# Power.net
KiCad netlist of a schematic drawn in Altium Designer
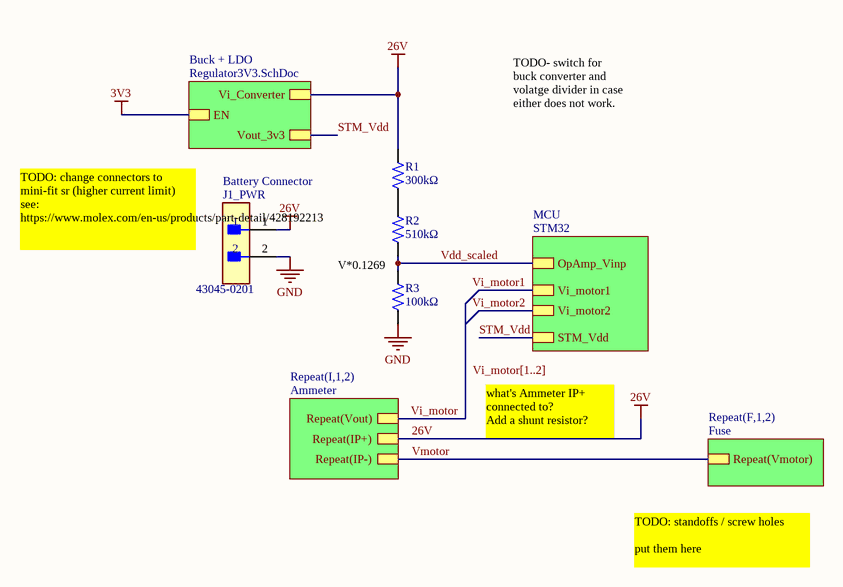
[diagram p0: Power.SchDoc]

(export (version "E")
  (design (tool "Eeschema 10.0.6"))
  (components
    (comp (ref "J1_PWR")
      (value "43045-0201")
      (footprint "FP-43045-0201-MFG")
      (description "CONN HEADER R/A 2POS")
      (libsource (lib "Altium Content Vault") (part "3bc925449376181038e59eaffc5286c"))
    )
    (comp (ref "R1")
      (value "0603WAF3003T5E")
      (footprint "RES-0603")
      (description "Resistor, 300kΩ, ±1%, 100mW, 75V, ±100ppm/℃, -55℃~+155℃, SMD 0603")
      (fields
        (field (name "MANUFACTURER") "Uniroyal")
        (field (name "JLCPCB PART NUMBER") "C23024")
        (field (name "RESISTANCE") "300kΩ")
      )
      (libsource (lib "jlcpcb_2024_10_resistors_basic") (part "0603WAF3003T5E"))
    )
    (comp (ref "R2")
      (value "0603WAF5103T5E")
      (footprint "RES-0603")
      (description "Resistor, 510kΩ, ±1%, 100mW, 75V, ±100ppm/℃, -55℃~+155℃, SMD 0603")
      (fields
        (field (name "MANUFACTURER") "Uniroyal")
        (field (name "JLCPCB PART NUMBER") "C23192")
        (field (name "RESISTANCE") "510kΩ")
      )
      (libsource (lib "jlcpcb_2024_10_resistors_basic") (part "0603WAF5103T5E"))
    )
    (comp (ref "R3")
      (value "0402WGF1003TCE")
      (footprint "RES-0402")
      (description "Resistor, 100kΩ, ±1%, 62.5mW, 50V, ±100ppm/℃, -55℃~+155℃, SMD 0402")
      (fields
        (field (name "MANUFACTURER") "Uniroyal")
        (field (name "JLCPCB PART NUMBER") "C25741")
        (field (name "RESISTANCE") "100kΩ")
      )
      (libsource (lib "jlcpcb_2024_10_resistors_basic") (part "0402WGF1003TCE"))
    )
  )
  (nets
    (net (code "3") (name "/Vdd_scaled") (class "Default")
      (node (ref "R2") (pin "1") (pinfunction "1_1") (pintype "passive"))
      (node (ref "R3") (pin "2") (pinfunction "2_2") (pintype "passive"))
    )
    (net (code "10") (name "26V") (class "Default")
      (node (ref "J1_PWR") (pin "1") (pinfunction "1_1") (pintype "passive"))
      (node (ref "R1") (pin "2") (pinfunction "2_2") (pintype "passive"))
    )
    (net (code "11") (name "GND") (class "Default")
      (node (ref "J1_PWR") (pin "2") (pinfunction "2_2") (pintype "passive"))
      (node (ref "R3") (pin "1") (pinfunction "1_1") (pintype "passive"))
    )
    (net (code "12") (name "Net-(R1-Pad1)") (class "Default")
      (node (ref "R1") (pin "1") (pinfunction "1_1") (pintype "passive"))
      (node (ref "R2") (pin "2") (pinfunction "2_2") (pintype "passive"))
    )
  )
)
